# Brushless_Controller.net
KiCad netlist of a schematic drawn in Altium Designer
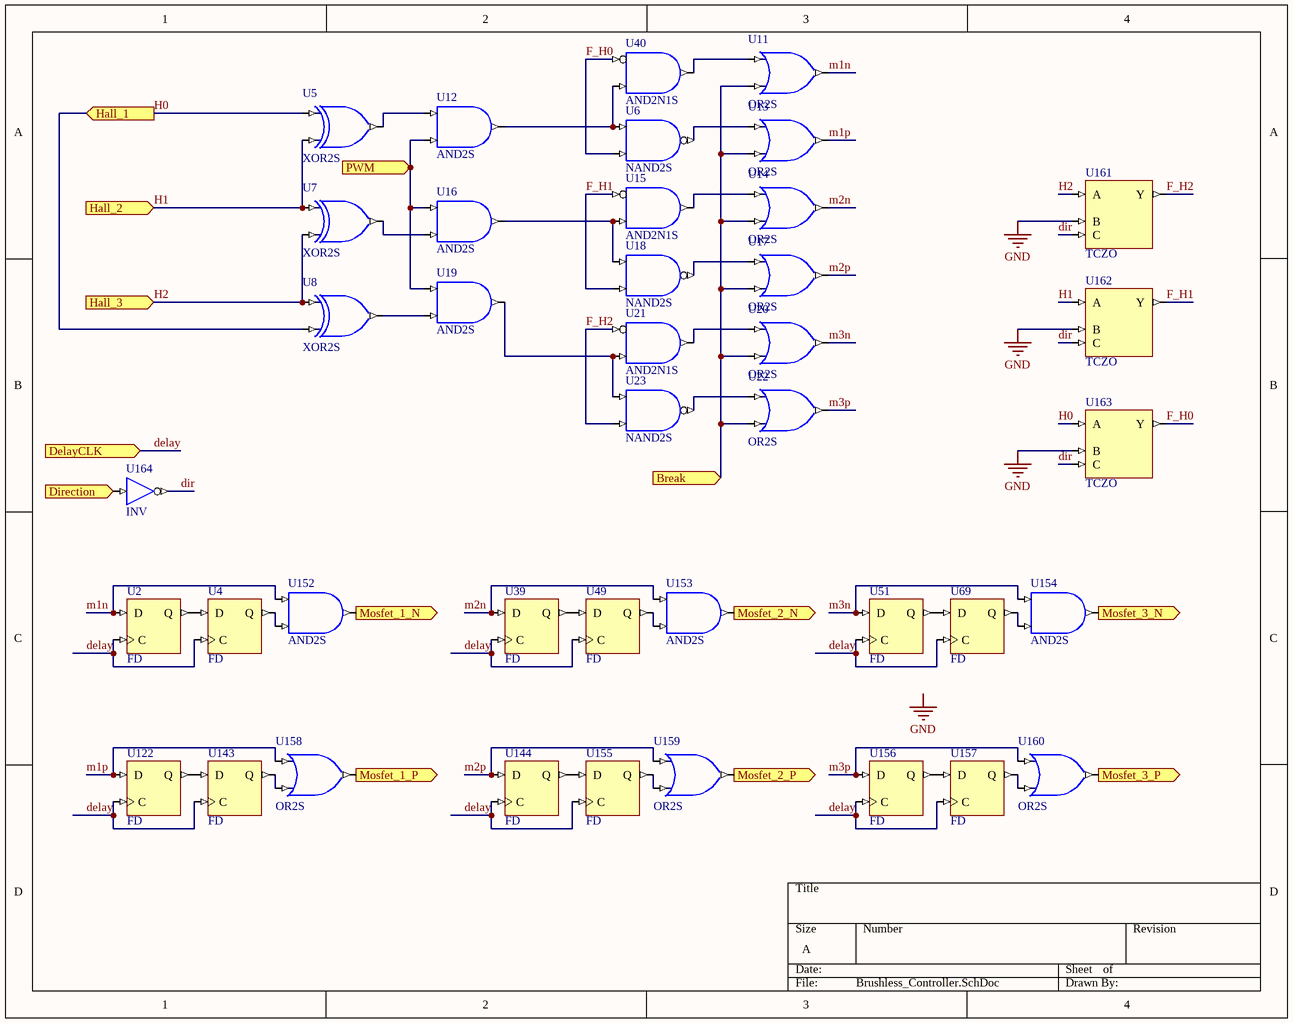
[diagram p0: Brushless_Controller.SchDoc]

(export (version "E")
  (design (tool "Eeschema 10.0.6"))
  (components
    (comp (ref "U2")
      (value "FD")
      (description "D-Type Flip-Flop")
      (fields (field (name "PUBLISHER") "Altium Limited"))
      (libsource (lib "FPGA Generic") (part "FD"))
    )
    (comp (ref "U4")
      (value "FD")
      (description "D-Type Flip-Flop")
      (fields (field (name "PUBLISHER") "Altium Limited"))
      (libsource (lib "FPGA Generic") (part "FD"))
    )
    (comp (ref "U5")
      (value "XOR2S")
      (description "2-Input Exclusive-OR Gate, Single Pin Version")
      (fields (field (name "PUBLISHER") "Altium Limited"))
      (libsource (lib "FPGA Generic") (part "XOR2S"))
    )
    (comp (ref "U6")
      (value "NAND2S")
      (description "2-Input NAND Gate, Single Pin Version")
      (fields (field (name "PUBLISHER") "Altium Limited"))
      (libsource (lib "FPGA Generic") (part "NAND2S"))
    )
    (comp (ref "U7")
      (value "XOR2S")
      (description "2-Input Exclusive-OR Gate, Single Pin Version")
      (fields (field (name "PUBLISHER") "Altium Limited"))
      (libsource (lib "FPGA Generic") (part "XOR2S"))
    )
    (comp (ref "U8")
      (value "XOR2S")
      (description "2-Input Exclusive-OR Gate, Single Pin Version")
      (fields (field (name "PUBLISHER") "Altium Limited"))
      (libsource (lib "FPGA Generic") (part "XOR2S"))
    )
    (comp (ref "U11")
      (value "OR2S")
      (description "2-Input OR Gate, Single Pin Version")
      (fields (field (name "PUBLISHER") "Altium Limited"))
      (libsource (lib "FPGA Generic") (part "OR2S"))
    )
    (comp (ref "U12")
      (value "AND2S")
      (description "2-Input AND Gate, Single Pin Version")
      (fields (field (name "PUBLISHER") "Altium Limited"))
      (libsource (lib "FPGA Generic") (part "AND2S"))
    )
    (comp (ref "U13")
      (value "OR2S")
      (description "2-Input OR Gate, Single Pin Version")
      (fields (field (name "PUBLISHER") "Altium Limited"))
      (libsource (lib "FPGA Generic") (part "OR2S"))
    )
    (comp (ref "U14")
      (value "OR2S")
      (description "2-Input OR Gate, Single Pin Version")
      (fields (field (name "PUBLISHER") "Altium Limited"))
      (libsource (lib "FPGA Generic") (part "OR2S"))
    )
    (comp (ref "U15")
      (value "AND2N1S")
      (description "2-Input AND Gate with Active Low A Input, Single Pin Version")
      (fields (field (name "PUBLISHER") "Altium Limited"))
      (libsource (lib "FPGA Generic") (part "AND2N1S"))
    )
    (comp (ref "U16")
      (value "AND2S")
      (description "2-Input AND Gate, Single Pin Version")
      (fields (field (name "PUBLISHER") "Altium Limited"))
      (libsource (lib "FPGA Generic") (part "AND2S"))
    )
    (comp (ref "U17")
      (value "OR2S")
      (description "2-Input OR Gate, Single Pin Version")
      (fields (field (name "PUBLISHER") "Altium Limited"))
      (libsource (lib "FPGA Generic") (part "OR2S"))
    )
    (comp (ref "U18")
      (value "NAND2S")
      (description "2-Input NAND Gate, Single Pin Version")
      (fields (field (name "PUBLISHER") "Altium Limited"))
      (libsource (lib "FPGA Generic") (part "NAND2S"))
    )
    (comp (ref "U19")
      (value "AND2S")
      (description "2-Input AND Gate, Single Pin Version")
      (fields (field (name "PUBLISHER") "Altium Limited"))
      (libsource (lib "FPGA Generic") (part "AND2S"))
    )
    (comp (ref "U20")
      (value "OR2S")
      (description "2-Input OR Gate, Single Pin Version")
      (fields (field (name "PUBLISHER") "Altium Limited"))
      (libsource (lib "FPGA Generic") (part "OR2S"))
    )
    (comp (ref "U21")
      (value "AND2N1S")
      (description "2-Input AND Gate with Active Low A Input, Single Pin Version")
      (fields (field (name "PUBLISHER") "Altium Limited"))
      (libsource (lib "FPGA Generic") (part "AND2N1S"))
    )
    (comp (ref "U22")
      (value "OR2S")
      (description "2-Input OR Gate, Single Pin Version")
      (fields (field (name "PUBLISHER") "Altium Limited"))
      (libsource (lib "FPGA Generic") (part "OR2S"))
    )
    (comp (ref "U23")
      (value "NAND2S")
      (description "2-Input NAND Gate, Single Pin Version")
      (fields (field (name "PUBLISHER") "Altium Limited"))
      (libsource (lib "FPGA Generic") (part "NAND2S"))
    )
    (comp (ref "U39")
      (value "FD")
      (description "D-Type Flip-Flop")
      (fields (field (name "PUBLISHER") "Altium Limited"))
      (libsource (lib "FPGA Generic") (part "FD"))
    )
    (comp (ref "U40")
      (value "AND2N1S")
      (description "2-Input AND Gate with Active Low A Input, Single Pin Version")
      (fields (field (name "PUBLISHER") "Altium Limited"))
      (libsource (lib "FPGA Generic") (part "AND2N1S"))
    )
    (comp (ref "U49")
      (value "FD")
      (description "D-Type Flip-Flop")
      (fields (field (name "PUBLISHER") "Altium Limited"))
      (libsource (lib "FPGA Generic") (part "FD"))
    )
    (comp (ref "U51")
      (value "FD")
      (description "D-Type Flip-Flop")
      (fields (field (name "PUBLISHER") "Altium Limited"))
      (libsource (lib "FPGA Generic") (part "FD"))
    )
    (comp (ref "U69")
      (value "FD")
      (description "D-Type Flip-Flop")
      (fields (field (name "PUBLISHER") "Altium Limited"))
      (libsource (lib "FPGA Generic") (part "FD"))
    )
    (comp (ref "U122")
      (value "FD")
      (description "D-Type Flip-Flop")
      (fields (field (name "PUBLISHER") "Altium Limited"))
      (libsource (lib "FPGA Generic") (part "FD"))
    )
    (comp (ref "U143")
      (value "FD")
      (description "D-Type Flip-Flop")
      (fields (field (name "PUBLISHER") "Altium Limited"))
      (libsource (lib "FPGA Generic") (part "FD"))
    )
    (comp (ref "U144")
      (value "FD")
      (description "D-Type Flip-Flop")
      (fields (field (name "PUBLISHER") "Altium Limited"))
      (libsource (lib "FPGA Generic") (part "FD"))
    )
    (comp (ref "U152")
      (value "AND2S")
      (description "2-Input AND Gate, Single Pin Version")
      (fields (field (name "PUBLISHER") "Altium Limited"))
      (libsource (lib "FPGA Generic") (part "AND2S"))
    )
    (comp (ref "U153")
      (value "AND2S")
      (description "2-Input AND Gate, Single Pin Version")
      (fields (field (name "PUBLISHER") "Altium Limited"))
      (libsource (lib "FPGA Generic") (part "AND2S"))
    )
    (comp (ref "U154")
      (value "AND2S")
      (description "2-Input AND Gate, Single Pin Version")
      (fields (field (name "PUBLISHER") "Altium Limited"))
      (libsource (lib "FPGA Generic") (part "AND2S"))
    )
    (comp (ref "U155")
      (value "FD")
      (description "D-Type Flip-Flop")
      (fields (field (name "PUBLISHER") "Altium Limited"))
      (libsource (lib "FPGA Generic") (part "FD"))
    )
    (comp (ref "U156")
      (value "FD")
      (description "D-Type Flip-Flop")
      (fields (field (name "PUBLISHER") "Altium Limited"))
      (libsource (lib "FPGA Generic") (part "FD"))
    )
    (comp (ref "U157")
      (value "FD")
      (description "D-Type Flip-Flop")
      (fields (field (name "PUBLISHER") "Altium Limited"))
      (libsource (lib "FPGA Generic") (part "FD"))
    )
    (comp (ref "U158")
      (value "OR2S")
      (description "2-Input OR Gate, Single Pin Version")
      (fields (field (name "PUBLISHER") "Altium Limited"))
      (libsource (lib "FPGA Generic") (part "OR2S"))
    )
    (comp (ref "U159")
      (value "OR2S")
      (description "2-Input OR Gate, Single Pin Version")
      (fields (field (name "PUBLISHER") "Altium Limited"))
      (libsource (lib "FPGA Generic") (part "OR2S"))
    )
    (comp (ref "U160")
      (value "OR2S")
      (description "2-Input OR Gate, Single Pin Version")
      (fields (field (name "PUBLISHER") "Altium Limited"))
      (libsource (lib "FPGA Generic") (part "OR2S"))
    )
    (comp (ref "U161")
      (value "TCZO")
      (description "True/Complement, Zero/One Element")
      (fields (field (name "PUBLISHER") "Altium Limited"))
      (libsource (lib "FPGA Generic") (part "TCZO"))
    )
    (comp (ref "U162")
      (value "TCZO")
      (description "True/Complement, Zero/One Element")
      (fields (field (name "PUBLISHER") "Altium Limited"))
      (libsource (lib "FPGA Generic") (part "TCZO"))
    )
    (comp (ref "U163")
      (value "TCZO")
      (description "True/Complement, Zero/One Element")
      (fields (field (name "PUBLISHER") "Altium Limited"))
      (libsource (lib "FPGA Generic") (part "TCZO"))
    )
    (comp (ref "U164")
      (value "INV")
      (description "Inverter")
      (fields (field (name "PUBLISHER") "Altium Limited"))
      (libsource (lib "FPGA Generic") (part "INV"))
    )
  )
  (nets
    (net (code "1") (name "/Break") (class "Default")
      (node (ref "U11") (pin "I1") (pinfunction "I1_I1") (pintype "input"))
      (node (ref "U13") (pin "I1") (pinfunction "I1_I1") (pintype "input"))
      (node (ref "U14") (pin "I1") (pinfunction "I1_I1") (pintype "input"))
      (node (ref "U17") (pin "I1") (pinfunction "I1_I1") (pintype "input"))
      (node (ref "U20") (pin "I1") (pinfunction "I1_I1") (pintype "input"))
      (node (ref "U22") (pin "I1") (pinfunction "I1_I1") (pintype "input"))
    )
    (net (code "2") (name "/Direction") (class "Default")
      (node (ref "U164") (pin "I") (pinfunction "I_I") (pintype "input"))
    )
    (net (code "3") (name "/F_H0") (class "Default")
      (node (ref "U163") (pin "Y") (pinfunction "Y_Y") (pintype "output"))
      (node (ref "U40") (pin "I0") (pinfunction "I0_I0") (pintype "input"))
      (node (ref "U6") (pin "I1") (pinfunction "I1_I1") (pintype "input"))
    )
    (net (code "4") (name "/F_H1") (class "Default")
      (node (ref "U15") (pin "I0") (pinfunction "I0_I0") (pintype "input"))
      (node (ref "U162") (pin "Y") (pinfunction "Y_Y") (pintype "output"))
      (node (ref "U18") (pin "I1") (pinfunction "I1_I1") (pintype "input"))
    )
    (net (code "5") (name "/F_H2") (class "Default")
      (node (ref "U161") (pin "Y") (pinfunction "Y_Y") (pintype "output"))
      (node (ref "U21") (pin "I0") (pinfunction "I0_I0") (pintype "input"))
      (node (ref "U23") (pin "I1") (pinfunction "I1_I1") (pintype "input"))
    )
    (net (code "6") (name "/H0") (class "Default")
      (node (ref "U163") (pin "A") (pinfunction "A_A") (pintype "input"))
      (node (ref "U5") (pin "I0") (pinfunction "I0_I0") (pintype "input"))
      (node (ref "U8") (pin "I1") (pinfunction "I1_I1") (pintype "input"))
    )
    (net (code "7") (name "/H1") (class "Default")
      (node (ref "U162") (pin "A") (pinfunction "A_A") (pintype "input"))
      (node (ref "U5") (pin "I1") (pinfunction "I1_I1") (pintype "input"))
      (node (ref "U7") (pin "I0") (pinfunction "I0_I0") (pintype "input"))
    )
    (net (code "8") (name "/H2") (class "Default")
      (node (ref "U161") (pin "A") (pinfunction "A_A") (pintype "input"))
      (node (ref "U7") (pin "I1") (pinfunction "I1_I1") (pintype "input"))
      (node (ref "U8") (pin "I0") (pinfunction "I0_I0") (pintype "input"))
    )
    (net (code "9") (name "/Mosfet_1_N") (class "Default")
      (node (ref "U152") (pin "O") (pinfunction "O_O") (pintype "output"))
    )
    (net (code "10") (name "/Mosfet_1_P") (class "Default")
      (node (ref "U158") (pin "O") (pinfunction "O_O") (pintype "output"))
    )
    (net (code "11") (name "/Mosfet_2_N") (class "Default")
      (node (ref "U153") (pin "O") (pinfunction "O_O") (pintype "output"))
    )
    (net (code "12") (name "/Mosfet_2_P") (class "Default")
      (node (ref "U159") (pin "O") (pinfunction "O_O") (pintype "output"))
    )
    (net (code "13") (name "/Mosfet_3_N") (class "Default")
      (node (ref "U154") (pin "O") (pinfunction "O_O") (pintype "output"))
    )
    (net (code "14") (name "/Mosfet_3_P") (class "Default")
      (node (ref "U160") (pin "O") (pinfunction "O_O") (pintype "output"))
    )
    (net (code "15") (name "/PWM") (class "Default")
      (node (ref "U12") (pin "I1") (pinfunction "I1_I1") (pintype "input"))
      (node (ref "U16") (pin "I0") (pinfunction "I0_I0") (pintype "input"))
      (node (ref "U19") (pin "I0") (pinfunction "I0_I0") (pintype "input"))
    )
    (net (code "16") (name "/delay") (class "Default")
      (node (ref "U122") (pin "C") (pinfunction "C_C") (pintype "input"))
      (node (ref "U143") (pin "C") (pinfunction "C_C") (pintype "input"))
      (node (ref "U144") (pin "C") (pinfunction "C_C") (pintype "input"))
      (node (ref "U155") (pin "C") (pinfunction "C_C") (pintype "input"))
      (node (ref "U156") (pin "C") (pinfunction "C_C") (pintype "input"))
      (node (ref "U157") (pin "C") (pinfunction "C_C") (pintype "input"))
      (node (ref "U2") (pin "C") (pinfunction "C_C") (pintype "input"))
      (node (ref "U39") (pin "C") (pinfunction "C_C") (pintype "input"))
      (node (ref "U4") (pin "C") (pinfunction "C_C") (pintype "input"))
      (node (ref "U49") (pin "C") (pinfunction "C_C") (pintype "input"))
      (node (ref "U51") (pin "C") (pinfunction "C_C") (pintype "input"))
      (node (ref "U69") (pin "C") (pinfunction "C_C") (pintype "input"))
    )
    (net (code "17") (name "/dir") (class "Default")
      (node (ref "U161") (pin "C") (pinfunction "C_C") (pintype "input"))
      (node (ref "U162") (pin "C") (pinfunction "C_C") (pintype "input"))
      (node (ref "U163") (pin "C") (pinfunction "C_C") (pintype "input"))
      (node (ref "U164") (pin "O") (pinfunction "O_O") (pintype "output"))
    )
    (net (code "18") (name "/m1n") (class "Default")
      (node (ref "U11") (pin "O") (pinfunction "O_O") (pintype "output"))
      (node (ref "U152") (pin "I0") (pinfunction "I0_I0") (pintype "input"))
      (node (ref "U2") (pin "D") (pinfunction "D_D") (pintype "input"))
    )
    (net (code "19") (name "/m1p") (class "Default")
      (node (ref "U122") (pin "D") (pinfunction "D_D") (pintype "input"))
      (node (ref "U13") (pin "O") (pinfunction "O_O") (pintype "output"))
      (node (ref "U158") (pin "I0") (pinfunction "I0_I0") (pintype "input"))
    )
    (net (code "20") (name "/m2n") (class "Default")
      (node (ref "U14") (pin "O") (pinfunction "O_O") (pintype "output"))
      (node (ref "U153") (pin "I0") (pinfunction "I0_I0") (pintype "input"))
      (node (ref "U39") (pin "D") (pinfunction "D_D") (pintype "input"))
    )
    (net (code "21") (name "/m2p") (class "Default")
      (node (ref "U144") (pin "D") (pinfunction "D_D") (pintype "input"))
      (node (ref "U159") (pin "I0") (pinfunction "I0_I0") (pintype "input"))
      (node (ref "U17") (pin "O") (pinfunction "O_O") (pintype "output"))
    )
    (net (code "22") (name "/m3n") (class "Default")
      (node (ref "U154") (pin "I0") (pinfunction "I0_I0") (pintype "input"))
      (node (ref "U20") (pin "O") (pinfunction "O_O") (pintype "output"))
      (node (ref "U51") (pin "D") (pinfunction "D_D") (pintype "input"))
    )
    (net (code "23") (name "/m3p") (class "Default")
      (node (ref "U156") (pin "D") (pinfunction "D_D") (pintype "input"))
      (node (ref "U160") (pin "I0") (pinfunction "I0_I0") (pintype "input"))
      (node (ref "U22") (pin "O") (pinfunction "O_O") (pintype "output"))
    )
    (net (code "24") (name "GND") (class "Default")
      (node (ref "U161") (pin "B") (pinfunction "B_B") (pintype "input"))
      (node (ref "U162") (pin "B") (pinfunction "B_B") (pintype "input"))
      (node (ref "U163") (pin "B") (pinfunction "B_B") (pintype "input"))
    )
    (net (code "25") (name "Net-(U2-PadQ)") (class "Default")
      (node (ref "U2") (pin "Q") (pinfunction "Q_Q") (pintype "output"))
      (node (ref "U4") (pin "D") (pinfunction "D_D") (pintype "input"))
    )
    (net (code "26") (name "Net-(U11-PadI0)") (class "Default")
      (node (ref "U11") (pin "I0") (pinfunction "I0_I0") (pintype "input"))
      (node (ref "U40") (pin "O") (pinfunction "O_O") (pintype "output"))
    )
    (net (code "27") (name "Net-(U12-PadI0)") (class "Default")
      (node (ref "U12") (pin "I0") (pinfunction "I0_I0") (pintype "input"))
      (node (ref "U5") (pin "O") (pinfunction "O_O") (pintype "output"))
    )
    (net (code "28") (name "Net-(U12-PadO)") (class "Default")
      (node (ref "U12") (pin "O") (pinfunction "O_O") (pintype "output"))
      (node (ref "U40") (pin "I1") (pinfunction "I1_I1") (pintype "input"))
      (node (ref "U6") (pin "I0") (pinfunction "I0_I0") (pintype "input"))
    )
    (net (code "29") (name "Net-(U13-PadI0)") (class "Default")
      (node (ref "U13") (pin "I0") (pinfunction "I0_I0") (pintype "input"))
      (node (ref "U6") (pin "O") (pinfunction "O_O") (pintype "output"))
    )
    (net (code "30") (name "Net-(U14-PadI0)") (class "Default")
      (node (ref "U14") (pin "I0") (pinfunction "I0_I0") (pintype "input"))
      (node (ref "U15") (pin "O") (pinfunction "O_O") (pintype "output"))
    )
    (net (code "31") (name "Net-(U15-PadI1)") (class "Default")
      (node (ref "U15") (pin "I1") (pinfunction "I1_I1") (pintype "input"))
      (node (ref "U16") (pin "O") (pinfunction "O_O") (pintype "output"))
      (node (ref "U18") (pin "I0") (pinfunction "I0_I0") (pintype "input"))
    )
    (net (code "32") (name "Net-(U16-PadI1)") (class "Default")
      (node (ref "U16") (pin "I1") (pinfunction "I1_I1") (pintype "input"))
      (node (ref "U7") (pin "O") (pinfunction "O_O") (pintype "output"))
    )
    (net (code "33") (name "Net-(U17-PadI0)") (class "Default")
      (node (ref "U17") (pin "I0") (pinfunction "I0_I0") (pintype "input"))
      (node (ref "U18") (pin "O") (pinfunction "O_O") (pintype "output"))
    )
    (net (code "34") (name "Net-(U19-PadI1)") (class "Default")
      (node (ref "U19") (pin "I1") (pinfunction "I1_I1") (pintype "input"))
      (node (ref "U8") (pin "O") (pinfunction "O_O") (pintype "output"))
    )
    (net (code "35") (name "Net-(U19-PadO)") (class "Default")
      (node (ref "U19") (pin "O") (pinfunction "O_O") (pintype "output"))
      (node (ref "U21") (pin "I1") (pinfunction "I1_I1") (pintype "input"))
      (node (ref "U23") (pin "I0") (pinfunction "I0_I0") (pintype "input"))
    )
    (net (code "36") (name "Net-(U20-PadI0)") (class "Default")
      (node (ref "U20") (pin "I0") (pinfunction "I0_I0") (pintype "input"))
      (node (ref "U21") (pin "O") (pinfunction "O_O") (pintype "output"))
    )
    (net (code "37") (name "Net-(U22-PadI0)") (class "Default")
      (node (ref "U22") (pin "I0") (pinfunction "I0_I0") (pintype "input"))
      (node (ref "U23") (pin "O") (pinfunction "O_O") (pintype "output"))
    )
    (net (code "38") (name "Net-(U39-PadQ)") (class "Default")
      (node (ref "U39") (pin "Q") (pinfunction "Q_Q") (pintype "output"))
      (node (ref "U49") (pin "D") (pinfunction "D_D") (pintype "input"))
    )
    (net (code "39") (name "Net-(U51-PadQ)") (class "Default")
      (node (ref "U51") (pin "Q") (pinfunction "Q_Q") (pintype "output"))
      (node (ref "U69") (pin "D") (pinfunction "D_D") (pintype "input"))
    )
    (net (code "40") (name "Net-(U122-PadQ)") (class "Default")
      (node (ref "U122") (pin "Q") (pinfunction "Q_Q") (pintype "output"))
      (node (ref "U143") (pin "D") (pinfunction "D_D") (pintype "input"))
    )
    (net (code "41") (name "Net-(U143-PadQ)") (class "Default")
      (node (ref "U143") (pin "Q") (pinfunction "Q_Q") (pintype "output"))
      (node (ref "U158") (pin "I1") (pinfunction "I1_I1") (pintype "input"))
    )
    (net (code "42") (name "Net-(U144-PadQ)") (class "Default")
      (node (ref "U144") (pin "Q") (pinfunction "Q_Q") (pintype "output"))
      (node (ref "U155") (pin "D") (pinfunction "D_D") (pintype "input"))
    )
    (net (code "43") (name "Net-(U152-PadI1)") (class "Default")
      (node (ref "U152") (pin "I1") (pinfunction "I1_I1") (pintype "input"))
      (node (ref "U4") (pin "Q") (pinfunction "Q_Q") (pintype "output"))
    )
    (net (code "44") (name "Net-(U153-PadI1)") (class "Default")
      (node (ref "U153") (pin "I1") (pinfunction "I1_I1") (pintype "input"))
      (node (ref "U49") (pin "Q") (pinfunction "Q_Q") (pintype "output"))
    )
    (net (code "45") (name "Net-(U154-PadI1)") (class "Default")
      (node (ref "U154") (pin "I1") (pinfunction "I1_I1") (pintype "input"))
      (node (ref "U69") (pin "Q") (pinfunction "Q_Q") (pintype "output"))
    )
    (net (code "46") (name "Net-(U155-PadQ)") (class "Default")
      (node (ref "U155") (pin "Q") (pinfunction "Q_Q") (pintype "output"))
      (node (ref "U159") (pin "I1") (pinfunction "I1_I1") (pintype "input"))
    )
    (net (code "47") (name "Net-(U156-PadQ)") (class "Default")
      (node (ref "U156") (pin "Q") (pinfunction "Q_Q") (pintype "output"))
      (node (ref "U157") (pin "D") (pinfunction "D_D") (pintype "input"))
    )
    (net (code "48") (name "Net-(U157-PadQ)") (class "Default")
      (node (ref "U157") (pin "Q") (pinfunction "Q_Q") (pintype "output"))
      (node (ref "U160") (pin "I1") (pinfunction "I1_I1") (pintype "input"))
    )
  )
)
